# lcd.net
KiCad netlist of a schematic drawn in Altium Designer
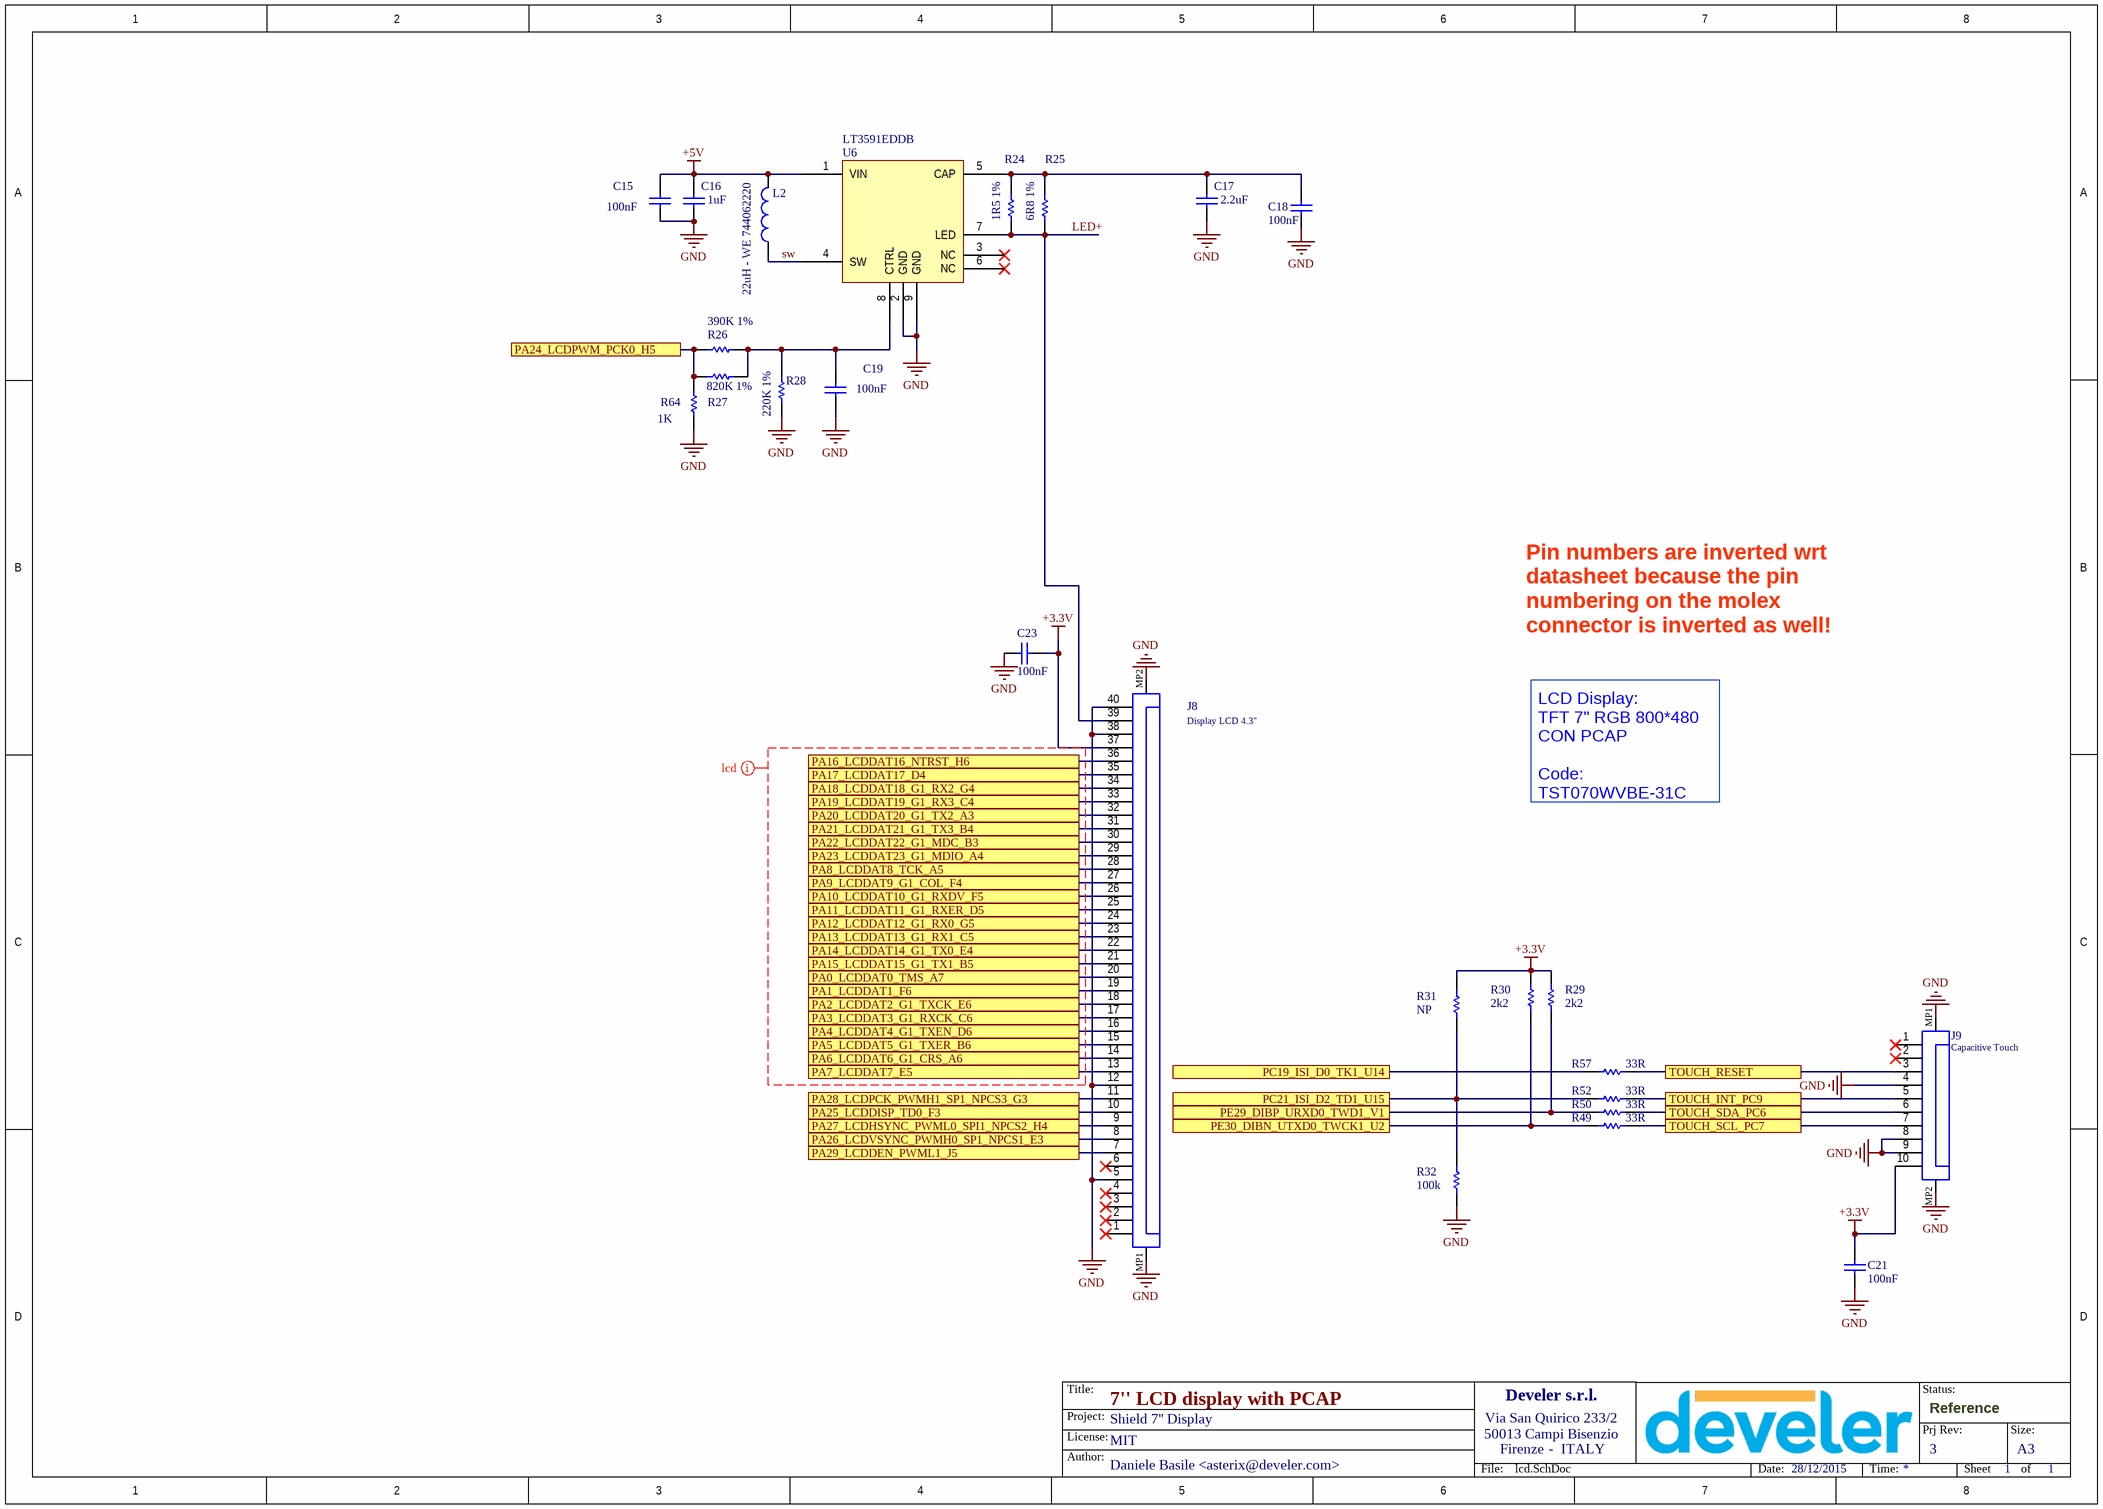
[diagram p0: lcd.SchDoc]

(export (version "E")
  (design (tool "Eeschema 10.0.6"))
  (components
    (comp (ref "C15")
      (value "100nF")
      (footprint "0603_[1608]")
      (description "Ceramic X7R 50V")
      (fields (field (name "PUBLISHER") "Altium Limited"))
      (libsource (lib "DEVELER_Library") (part "Cap"))
    )
    (comp (ref "C16")
      (value "1uF")
      (footprint "0603_[1608]")
      (description "Ceramic X7R, X5R 16V")
      (fields (field (name "PUBLISHER") "Altium Limited"))
      (libsource (lib "DEVELER_Library") (part "Cap"))
    )
    (comp (ref "C17")
      (value "2.2uF")
      (footprint "1210_[3225]")
      (description "Ceramic X7R, X5R 50V")
      (fields (field (name "PUBLISHER") "Altium Limited"))
      (libsource (lib "DEVELER_Library") (part "Cap"))
    )
    (comp (ref "C18")
      (value "100nF")
      (footprint "0603_[1608]")
      (description "Ceramic X7R 50V")
      (fields (field (name "PUBLISHER") "Altium Limited"))
      (libsource (lib "DEVELER_Library") (part "Cap"))
    )
    (comp (ref "C19")
      (value "100nF")
      (footprint "0603_[1608]")
      (description "Ceramic X7R 50V")
      (fields (field (name "PUBLISHER") "Altium Limited"))
      (libsource (lib "DEVELER_Library") (part "Cap"))
    )
    (comp (ref "C21")
      (value "100nF")
      (footprint "0603_[1608]")
      (description "Ceramic X7R 50V")
      (fields (field (name "PUBLISHER") "Altium Limited"))
      (libsource (lib "DEVELER_Library") (part "Cap"))
    )
    (comp (ref "C23")
      (value "100nF")
      (footprint "0603_[1608]")
      (description "Ceramic X7R 50V")
      (fields (field (name "PUBLISHER") "Altium Limited"))
      (libsource (lib "DEVELER_Library") (part "Cap"))
    )
    (comp (ref "J8")
      (value "Display LCD 4.3''")
      (footprint "FCC-ZIF_40PIN_0.5MM_TOP_LOWPROFILE")
      (fields (field (name "PART NUMBER") "687140183622") (field (name "PUBLISHER") "Wurth Elektronik"))
      (libsource (lib "develer_library") (part "FPC-ZIF_40PIN_1MM"))
    )
    (comp (ref "J9")
      (value "Capacitive Touch")
      (footprint "FCC-ZIF_10PIN_0.5MM_LOW_PROFILE")
      (description "SMT ZIF Connectors Low Profile WR-FPC, Horizontal, BOT Contact, pitch 0.5 mm, 10 pins")
      (fields (field (name "PART NUMBER") "687110183722") (field (name "PUBLISHER") "Wurth Elektronik"))
      (libsource (lib "develer_library") (part "FPC-ZIF_10PIN_0.5MM"))
    )
    (comp (ref "L2")
      (value "22uH - WE 744062220")
      (footprint "WE-TPC-6823-X")
      (description "Power Inductor")
      (libsource (lib "DEVELER_Library") (part "Inductor"))
    )
    (comp (ref "R24")
      (value "1R5 1%")
      (footprint "0603_[1608]")
      (description "Resistor 0.125W")
      (fields (field (name "PUBLISHER") "Altium Limited"))
      (libsource (lib "DEVELER_Library") (part "Res1"))
    )
    (comp (ref "R25")
      (value "6R8 1%")
      (footprint "0603_[1608]")
      (description "Resistor 0.125W")
      (fields (field (name "PUBLISHER") "Altium Limited"))
      (libsource (lib "DEVELER_Library") (part "Res1"))
    )
    (comp (ref "R26")
      (value "390K 1%")
      (footprint "0603_[1608]")
      (description "Resistor")
      (fields (field (name "PUBLISHER") "Altium Limited"))
      (libsource (lib "DEVELER_Library") (part "Res1"))
    )
    (comp (ref "R27")
      (value "820K 1%")
      (footprint "0603_[1608]")
      (description "Resistor")
      (fields (field (name "PUBLISHER") "Altium Limited"))
      (libsource (lib "DEVELER_Library") (part "Res1"))
    )
    (comp (ref "R28")
      (value "220K 1%")
      (footprint "0603_[1608]")
      (description "Resistor")
      (fields (field (name "PUBLISHER") "Altium Limited"))
      (libsource (lib "DEVELER_Library") (part "Res1"))
    )
    (comp (ref "R29")
      (value "2k2")
      (footprint "0603_[1608]")
      (description "Resistor 0.125W")
      (fields (field (name "PUBLISHER") "Altium Limited"))
      (libsource (lib "DEVELER_Library") (part "Res1"))
    )
    (comp (ref "R30")
      (value "2k2")
      (footprint "0603_[1608]")
      (description "Resistor 0.125W")
      (fields (field (name "PUBLISHER") "Altium Limited"))
      (libsource (lib "DEVELER_Library") (part "Res1"))
    )
    (comp (ref "R31")
      (value "NP")
      (footprint "0603_[1608]")
      (description "Resistor 0.125W")
      (fields (field (name "PUBLISHER") "Altium Limited"))
      (libsource (lib "DEVELER_Library") (part "Res1"))
    )
    (comp (ref "R32")
      (value "100k")
      (footprint "0603_[1608]")
      (description "Resistor 0.125W")
      (fields (field (name "PUBLISHER") "Altium Limited"))
      (libsource (lib "DEVELER_Library") (part "Res1"))
    )
    (comp (ref "R49")
      (value "33R")
      (footprint "0603_[1608]")
      (description "Resistor")
      (fields (field (name "PUBLISHER") "Altium Limited"))
      (libsource (lib "DEVELER_Library") (part "Res1"))
    )
    (comp (ref "R50")
      (value "33R")
      (footprint "0603_[1608]")
      (description "Resistor")
      (fields (field (name "PUBLISHER") "Altium Limited"))
      (libsource (lib "DEVELER_Library") (part "Res1"))
    )
    (comp (ref "R52")
      (value "33R")
      (footprint "0603_[1608]")
      (description "Resistor")
      (fields (field (name "PUBLISHER") "Altium Limited"))
      (libsource (lib "DEVELER_Library") (part "Res1"))
    )
    (comp (ref "R57")
      (value "33R")
      (footprint "0603_[1608]")
      (description "Resistor")
      (fields (field (name "PUBLISHER") "Altium Limited"))
      (libsource (lib "DEVELER_Library") (part "Res1"))
    )
    (comp (ref "R64")
      (value "1K")
      (footprint "0603_[1608]")
      (description "Resistor")
      (fields (field (name "PUBLISHER") "Altium Limited"))
      (libsource (lib "project42_lib") (part "Res1"))
    )
    (comp (ref "U6")
      (value "LT3591EDDB")
      (footprint "PQFN50P300X200X75_HS-9L")
      (description "White LED Driver with Integrated Schottky")
      (libsource (lib "DEVELER_Library") (part "LT3591"))
    )
  )
  (nets
    (net (code "1") (name "+3.3V") (class "Default")
      (node (ref "C21") (pin "1") (pinfunction "1_1") (pintype "passive"))
      (node (ref "C23") (pin "1") (pinfunction "1_1") (pintype "passive"))
      (node (ref "J8") (pin "37") (pinfunction "37_37") (pintype "passive"))
      (node (ref "J9") (pin "10") (pinfunction "10_10") (pintype "passive"))
      (node (ref "R29") (pin "1") (pinfunction "1_1") (pintype "passive"))
      (node (ref "R30") (pin "1") (pinfunction "1_1") (pintype "passive"))
      (node (ref "R31") (pin "1") (pinfunction "1_1") (pintype "passive"))
    )
    (net (code "2") (name "+5V") (class "Default")
      (node (ref "C15") (pin "2") (pinfunction "2_2") (pintype "passive"))
      (node (ref "C16") (pin "2") (pinfunction "2_2") (pintype "passive"))
      (node (ref "L2") (pin "2") (pinfunction "2_2") (pintype "passive"))
      (node (ref "U6") (pin "1") (pinfunction "VIN_1") (pintype "power_in"))
    )
    (net (code "3") (name "/LED+") (class "Default")
      (node (ref "J8") (pin "39") (pinfunction "39_39") (pintype "passive"))
      (node (ref "R24") (pin "1") (pinfunction "1_1") (pintype "passive"))
      (node (ref "R25") (pin "1") (pinfunction "1_1") (pintype "passive"))
      (node (ref "U6") (pin "7") (pinfunction "LED_7") (pintype "passive"))
    )
    (net (code "4") (name "/PA0_LCDDAT0_TMS_A7") (class "Default")
      (node (ref "J8") (pin "20") (pinfunction "20_20") (pintype "passive"))
    )
    (net (code "5") (name "/PA1_LCDDAT1_F6") (class "Default")
      (node (ref "J8") (pin "19") (pinfunction "19_19") (pintype "passive"))
    )
    (net (code "6") (name "/PA2_LCDDAT2_G1_TXCK_E6") (class "Default")
      (node (ref "J8") (pin "18") (pinfunction "18_18") (pintype "passive"))
    )
    (net (code "7") (name "/PA3_LCDDAT3_G1_RXCK_C6") (class "Default")
      (node (ref "J8") (pin "17") (pinfunction "17_17") (pintype "passive"))
    )
    (net (code "8") (name "/PA4_LCDDAT4_G1_TXEN_D6") (class "Default")
      (node (ref "J8") (pin "16") (pinfunction "16_16") (pintype "passive"))
    )
    (net (code "9") (name "/PA5_LCDDAT5_G1_TXER_B6") (class "Default")
      (node (ref "J8") (pin "15") (pinfunction "15_15") (pintype "passive"))
    )
    (net (code "10") (name "/PA6_LCDDAT6_G1_CRS_A6") (class "Default")
      (node (ref "J8") (pin "14") (pinfunction "14_14") (pintype "passive"))
    )
    (net (code "11") (name "/PA7_LCDDAT7_E5") (class "Default")
      (node (ref "J8") (pin "13") (pinfunction "13_13") (pintype "passive"))
    )
    (net (code "12") (name "/PA8_LCDDAT8_TCK_A5") (class "Default")
      (node (ref "J8") (pin "28") (pinfunction "28_28") (pintype "passive"))
    )
    (net (code "13") (name "/PA9_LCDDAT9_G1_COL_F4") (class "Default")
      (node (ref "J8") (pin "27") (pinfunction "27_27") (pintype "passive"))
    )
    (net (code "14") (name "/PA10_LCDDAT10_G1_RXDV_F5") (class "Default")
      (node (ref "J8") (pin "26") (pinfunction "26_26") (pintype "passive"))
    )
    (net (code "15") (name "/PA11_LCDDAT11_G1_RXER_D5") (class "Default")
      (node (ref "J8") (pin "25") (pinfunction "25_25") (pintype "passive"))
    )
    (net (code "16") (name "/PA12_LCDDAT12_G1_RX0_G5") (class "Default")
      (node (ref "J8") (pin "24") (pinfunction "24_24") (pintype "passive"))
    )
    (net (code "17") (name "/PA13_LCDDAT13_G1_RX1_C5") (class "Default")
      (node (ref "J8") (pin "23") (pinfunction "23_23") (pintype "passive"))
    )
    (net (code "18") (name "/PA14_LCDDAT14_G1_TX0_E4") (class "Default")
      (node (ref "J8") (pin "22") (pinfunction "22_22") (pintype "passive"))
    )
    (net (code "19") (name "/PA15_LCDDAT15_G1_TX1_B5") (class "Default")
      (node (ref "J8") (pin "21") (pinfunction "21_21") (pintype "passive"))
    )
    (net (code "20") (name "/PA16_LCDDAT16_NTRST_H6") (class "Default")
      (node (ref "J8") (pin "36") (pinfunction "36_36") (pintype "passive"))
    )
    (net (code "21") (name "/PA17_LCDDAT17_D4") (class "Default")
      (node (ref "J8") (pin "35") (pinfunction "35_35") (pintype "passive"))
    )
    (net (code "22") (name "/PA18_LCDDAT18_G1_RX2_G4") (class "Default")
      (node (ref "J8") (pin "34") (pinfunction "34_34") (pintype "passive"))
    )
    (net (code "23") (name "/PA19_LCDDAT19_G1_RX3_C4") (class "Default")
      (node (ref "J8") (pin "33") (pinfunction "33_33") (pintype "passive"))
    )
    (net (code "24") (name "/PA20_LCDDAT20_G1_TX2_A3") (class "Default")
      (node (ref "J8") (pin "32") (pinfunction "32_32") (pintype "passive"))
    )
    (net (code "25") (name "/PA21_LCDDAT21_G1_TX3_B4") (class "Default")
      (node (ref "J8") (pin "31") (pinfunction "31_31") (pintype "passive"))
    )
    (net (code "26") (name "/PA22_LCDDAT22_G1_MDC_B3") (class "Default")
      (node (ref "J8") (pin "30") (pinfunction "30_30") (pintype "passive"))
    )
    (net (code "27") (name "/PA23_LCDDAT23_G1_MDIO_A4") (class "Default")
      (node (ref "J8") (pin "29") (pinfunction "29_29") (pintype "passive"))
    )
    (net (code "28") (name "/PA24_LCDPWM_PCK0_H5") (class "Default")
      (node (ref "R26") (pin "2") (pinfunction "2_2") (pintype "passive"))
      (node (ref "R27") (pin "1") (pinfunction "1_1") (pintype "passive"))
      (node (ref "R64") (pin "1") (pinfunction "1_1") (pintype "passive"))
    )
    (net (code "29") (name "/PA25_LCDDISP_TD0_F3") (class "Default")
      (node (ref "J8") (pin "10") (pinfunction "10_10") (pintype "passive"))
    )
    (net (code "30") (name "/PA26_LCDVSYNC_PWMH0_SP1_NPCS1_E3") (class "Default")
      (node (ref "J8") (pin "8") (pinfunction "8_8") (pintype "passive"))
    )
    (net (code "31") (name "/PA27_LCDHSYNC_PWML0_SPI1_NPCS2_H4") (class "Default")
      (node (ref "J8") (pin "9") (pinfunction "9_9") (pintype "passive"))
    )
    (net (code "32") (name "/PA28_LCDPCK_PWMH1_SP1_NPCS3_G3") (class "Default")
      (node (ref "J8") (pin "11") (pinfunction "11_11") (pintype "passive"))
    )
    (net (code "33") (name "/PA29_LCDDEN_PWML1_J5") (class "Default")
      (node (ref "J8") (pin "7") (pinfunction "7_7") (pintype "passive"))
    )
    (net (code "34") (name "/PC19_ISI_D0_TK1_U14") (class "Default")
      (node (ref "R57") (pin "2") (pinfunction "2_2") (pintype "passive"))
    )
    (net (code "35") (name "/PC21_ISI_D2_TD1_U15") (class "Default")
      (node (ref "R31") (pin "2") (pinfunction "2_2") (pintype "passive"))
      (node (ref "R32") (pin "1") (pinfunction "1_1") (pintype "passive"))
      (node (ref "R52") (pin "2") (pinfunction "2_2") (pintype "passive"))
    )
    (net (code "36") (name "/PE29_DIBP_URXD0_TWD1_V1") (class "Default")
      (node (ref "R29") (pin "2") (pinfunction "2_2") (pintype "passive"))
      (node (ref "R50") (pin "2") (pinfunction "2_2") (pintype "passive"))
    )
    (net (code "37") (name "/PE30_DIBN_UTXD0_TWCK1_U2") (class "Default")
      (node (ref "R30") (pin "2") (pinfunction "2_2") (pintype "passive"))
      (node (ref "R49") (pin "2") (pinfunction "2_2") (pintype "passive"))
    )
    (net (code "38") (name "/TOUCH_INT_PC9") (class "Default")
      (node (ref "J9") (pin "5") (pinfunction "5_5") (pintype "passive"))
      (node (ref "R52") (pin "1") (pinfunction "1_1") (pintype "passive"))
    )
    (net (code "39") (name "/TOUCH_RESET") (class "Default")
      (node (ref "J9") (pin "3") (pinfunction "3_3") (pintype "passive"))
      (node (ref "R57") (pin "1") (pinfunction "1_1") (pintype "passive"))
    )
    (net (code "40") (name "/TOUCH_SCL_PC7") (class "Default")
      (node (ref "J9") (pin "7") (pinfunction "7_7") (pintype "passive"))
      (node (ref "R49") (pin "1") (pinfunction "1_1") (pintype "passive"))
    )
    (net (code "41") (name "/TOUCH_SDA_PC6") (class "Default")
      (node (ref "J9") (pin "6") (pinfunction "6_6") (pintype "passive"))
      (node (ref "R50") (pin "1") (pinfunction "1_1") (pintype "passive"))
    )
    (net (code "42") (name "/sw") (class "Default")
      (node (ref "L2") (pin "1") (pinfunction "1_1") (pintype "passive"))
      (node (ref "U6") (pin "4") (pinfunction "SW_4") (pintype "passive"))
    )
    (net (code "43") (name "GND") (class "Default")
      (node (ref "C15") (pin "1") (pinfunction "1_1") (pintype "passive"))
      (node (ref "C16") (pin "1") (pinfunction "1_1") (pintype "passive"))
      (node (ref "C17") (pin "1") (pinfunction "1_1") (pintype "passive"))
      (node (ref "C18") (pin "1") (pinfunction "1_1") (pintype "passive"))
      (node (ref "C19") (pin "1") (pinfunction "1_1") (pintype "passive"))
      (node (ref "C21") (pin "2") (pinfunction "2_2") (pintype "passive"))
      (node (ref "C23") (pin "2") (pinfunction "2_2") (pintype "passive"))
      (node (ref "J8") (pin "12") (pinfunction "12_12") (pintype "passive"))
      (node (ref "J8") (pin "38") (pinfunction "38_38") (pintype "passive"))
      (node (ref "J8") (pin "40") (pinfunction "40_40") (pintype "passive"))
      (node (ref "J8") (pin "5") (pinfunction "5_5") (pintype "passive"))
      (node (ref "J8") (pin "MP1") (pinfunction "MP1_MP1") (pintype "passive"))
      (node (ref "J8") (pin "MP2") (pinfunction "MP2_MP2") (pintype "passive"))
      (node (ref "J9") (pin "4") (pinfunction "4_4") (pintype "passive"))
      (node (ref "J9") (pin "8") (pinfunction "8_8") (pintype "passive"))
      (node (ref "J9") (pin "9") (pinfunction "9_9") (pintype "passive"))
      (node (ref "J9") (pin "MP1") (pinfunction "MP1_MP1") (pintype "passive"))
      (node (ref "J9") (pin "MP2") (pinfunction "MP2_MP2") (pintype "passive"))
      (node (ref "R28") (pin "2") (pinfunction "2_2") (pintype "passive"))
      (node (ref "R32") (pin "2") (pinfunction "2_2") (pintype "passive"))
      (node (ref "R64") (pin "2") (pinfunction "2_2") (pintype "passive"))
      (node (ref "U6") (pin "2") (pinfunction "GND_2") (pintype "power_in"))
      (node (ref "U6") (pin "9") (pinfunction "GND_9") (pintype "power_in"))
    )
    (net (code "44") (name "Net-(U6-CAP)") (class "Default")
      (node (ref "C17") (pin "2") (pinfunction "2_2") (pintype "passive"))
      (node (ref "C18") (pin "2") (pinfunction "2_2") (pintype "passive"))
      (node (ref "R24") (pin "2") (pinfunction "2_2") (pintype "passive"))
      (node (ref "R25") (pin "2") (pinfunction "2_2") (pintype "passive"))
      (node (ref "U6") (pin "5") (pinfunction "CAP_5") (pintype "passive"))
    )
    (net (code "45") (name "Net-(U6-CTRL)") (class "Default")
      (node (ref "C19") (pin "2") (pinfunction "2_2") (pintype "passive"))
      (node (ref "R26") (pin "1") (pinfunction "1_1") (pintype "passive"))
      (node (ref "R27") (pin "2") (pinfunction "2_2") (pintype "passive"))
      (node (ref "R28") (pin "1") (pinfunction "1_1") (pintype "passive"))
      (node (ref "U6") (pin "8") (pinfunction "CTRL_8") (pintype "passive"))
    )
    (net (code "46") (name "unconnected-(J8-Pad1)") (class "Default")
      (node (ref "J8") (pin "1") (pinfunction "1_1") (pintype "passive+no_connect"))
    )
    (net (code "47") (name "unconnected-(J8-Pad2)") (class "Default")
      (node (ref "J8") (pin "2") (pinfunction "2_2") (pintype "passive+no_connect"))
    )
    (net (code "48") (name "unconnected-(J8-Pad3)") (class "Default")
      (node (ref "J8") (pin "3") (pinfunction "3_3") (pintype "passive+no_connect"))
    )
    (net (code "49") (name "unconnected-(J8-Pad4)") (class "Default")
      (node (ref "J8") (pin "4") (pinfunction "4_4") (pintype "passive+no_connect"))
    )
    (net (code "50") (name "unconnected-(J8-Pad6)") (class "Default")
      (node (ref "J8") (pin "6") (pinfunction "6_6") (pintype "passive+no_connect"))
    )
    (net (code "51") (name "unconnected-(J9-Pad1)") (class "Default")
      (node (ref "J9") (pin "1") (pinfunction "1_1") (pintype "passive+no_connect"))
    )
    (net (code "52") (name "unconnected-(J9-Pad2)") (class "Default")
      (node (ref "J9") (pin "2") (pinfunction "2_2") (pintype "passive+no_connect"))
    )
    (net (code "53") (name "unconnected-(U6-NC-Pad3)") (class "Default")
      (node (ref "U6") (pin "3") (pinfunction "NC_3") (pintype "passive+no_connect"))
    )
    (net (code "54") (name "unconnected-(U6-NC-Pad6)") (class "Default")
      (node (ref "U6") (pin "6") (pinfunction "NC_6") (pintype "passive+no_connect"))
    )
  )
)
